# 1-Schematic_attiny_programmer.net
KiCad netlist of a schematic drawn in EasyEDA
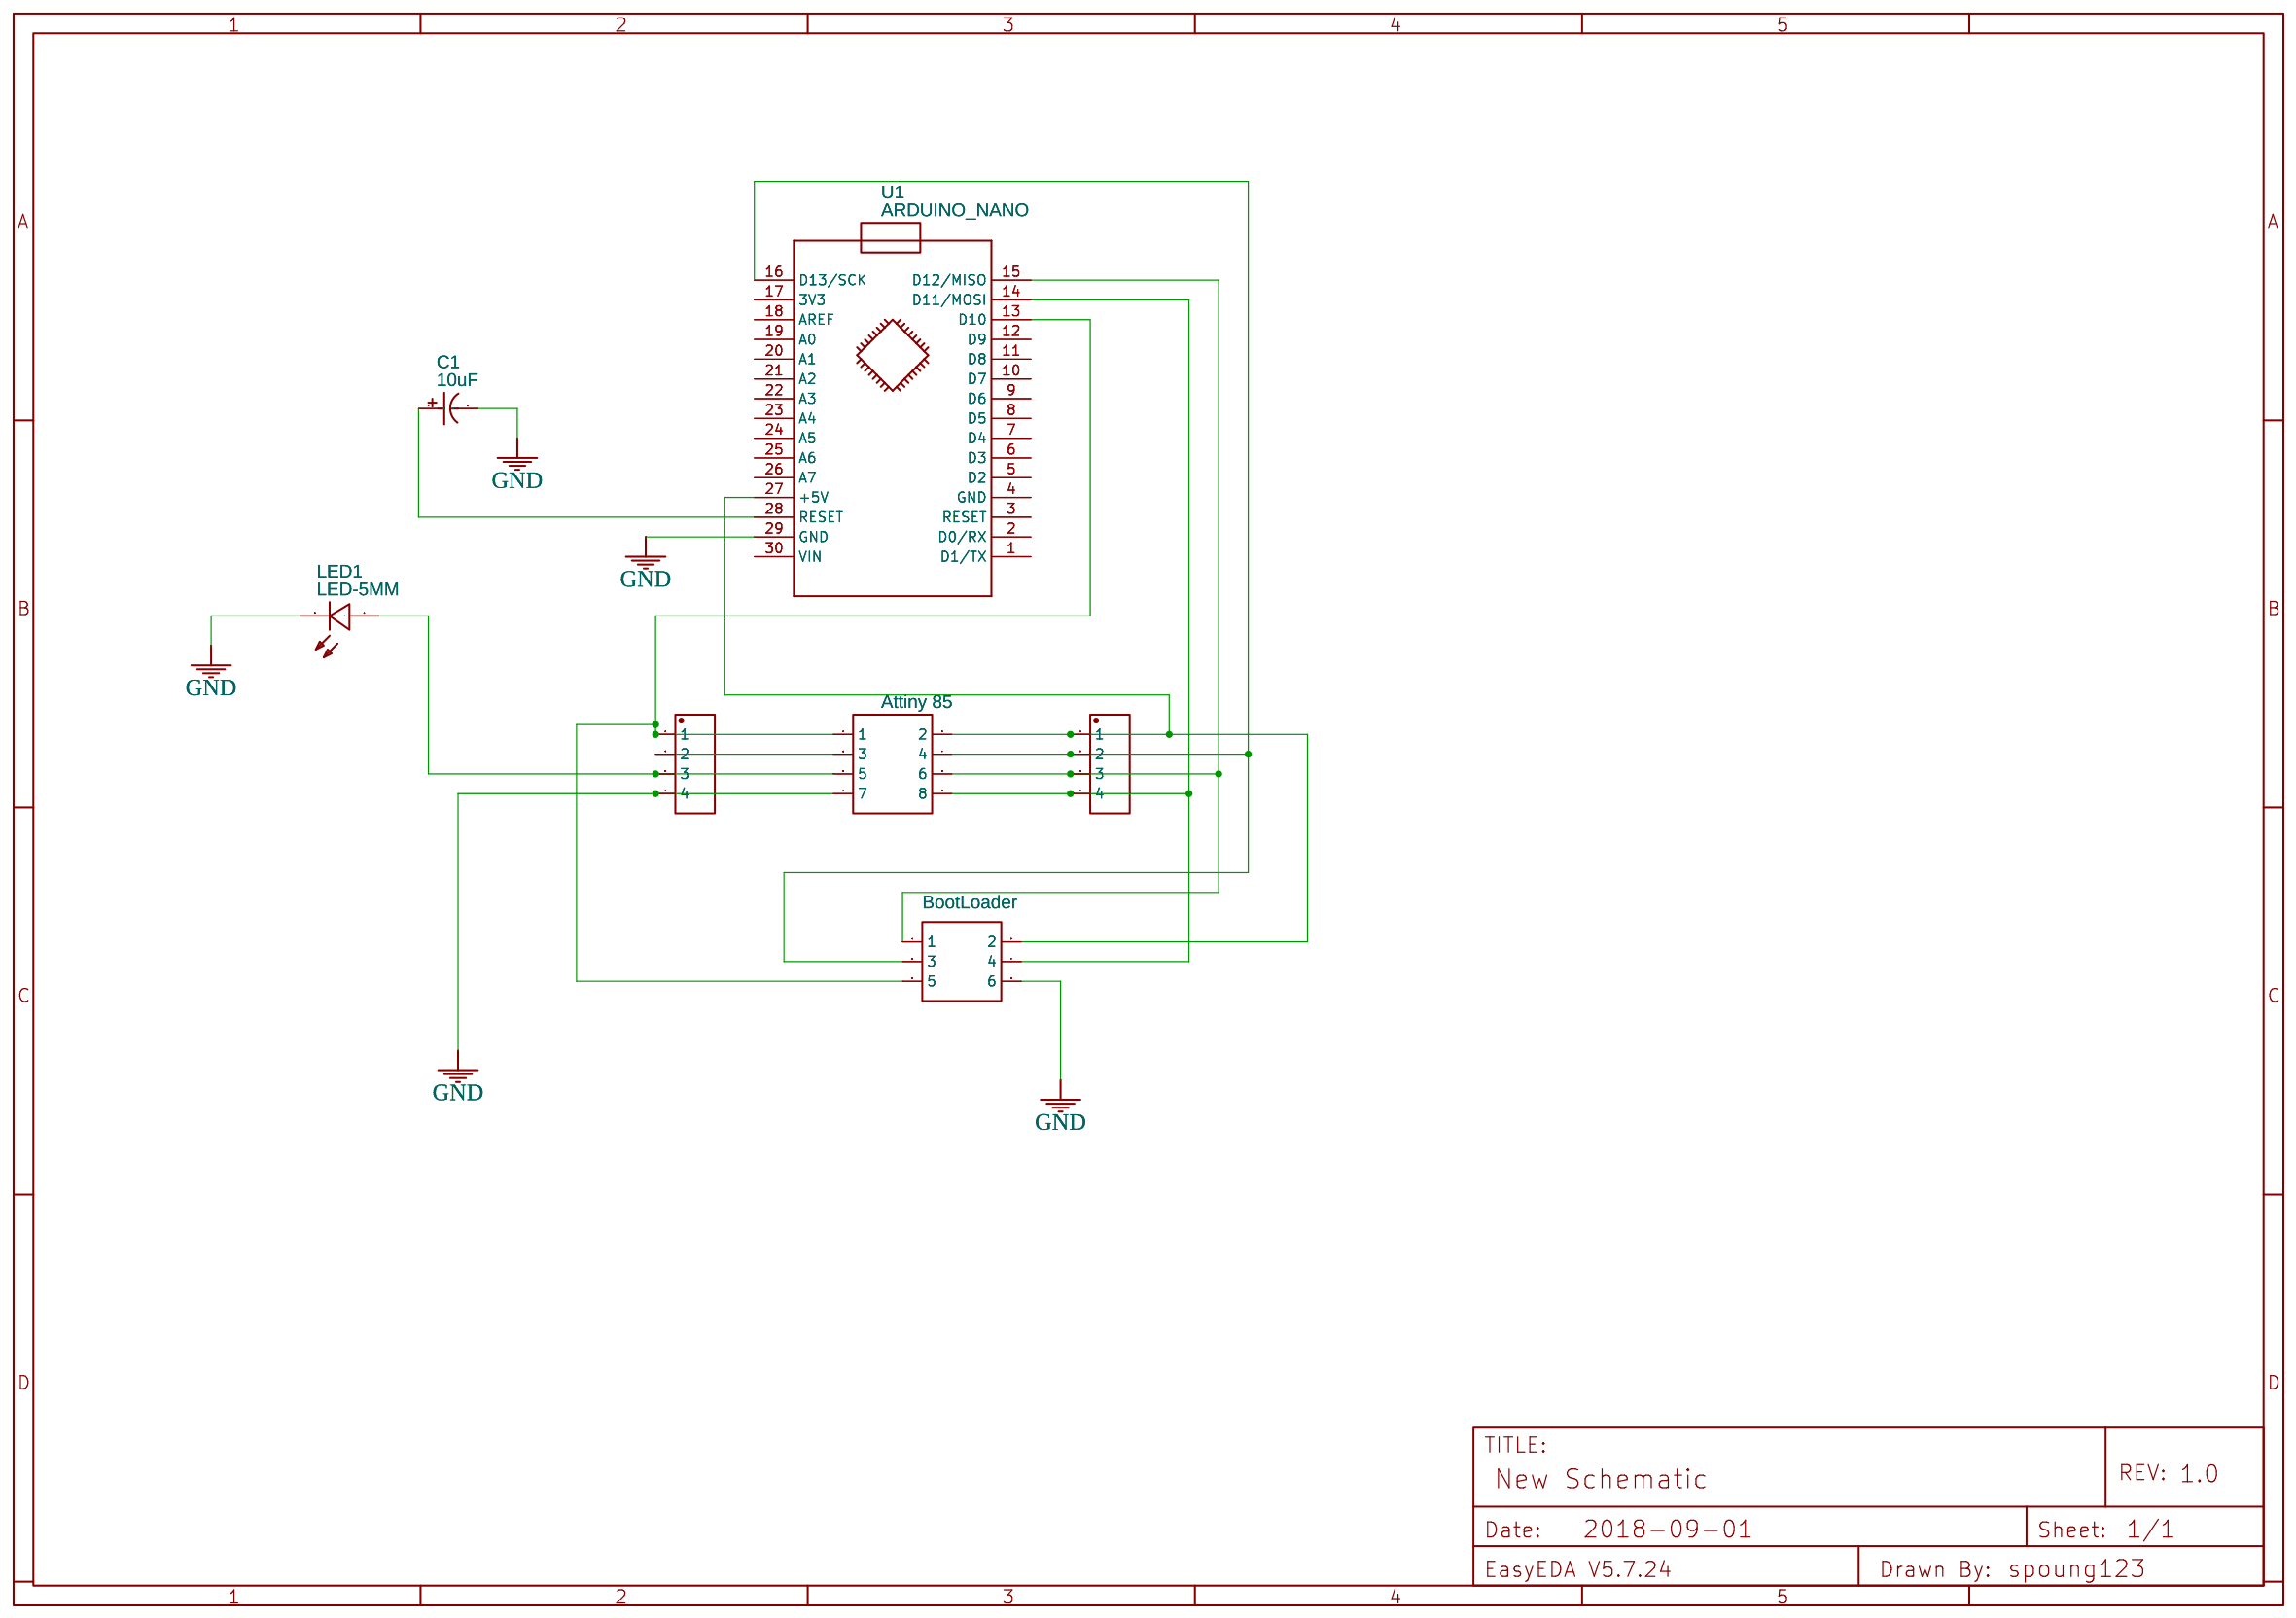
[diagram p0: schematic sheet]

(export (version "E")
  (design (tool "Eeschema 10.0.6"))
  (components
    (comp (ref "C1")
      (value "10uF")
      (fields (field (name "BOM_Manufacturer Part") "10uf/100V") (field (name "BOM_Supplier Part") "C2029"))
      (libsource (lib "") (part "10uf/100V"))
    )
    (comp (ref "H1")
      (value "Attiny 85")
      (fields
        (field (name "BOM_Manufacturer Part") "220S-2*4P H=8.5MM Ytype Gold-plated")
        (field (name "BOM_Supplier Part") "C124422")
      )
      (libsource (lib "") (part "Unknown_445_380"))
    )
    (comp (ref "H2")
      (value "Header-Male-2.54_1x4")
      (fields
        (field (name "BOM_Manufacturer Part") "210S-1*4P L=11.6MMGold-plated black")
        (field (name "BOM_Supplier Part") "C124378")
      )
      (libsource (lib "") (part "Unknown_550_380"))
    )
    (comp (ref "H3")
      (value "Header-Male-2.54_1x4")
      (fields
        (field (name "BOM_Manufacturer Part") "210S-1*4P L=11.6MMGold-plated black")
        (field (name "BOM_Supplier Part") "C124378")
      )
      (libsource (lib "") (part "Unknown_340_380"))
    )
    (comp (ref "LED1")
      (value "LED-5MM")
      (fields (field (name "BOM_Manufacturer Part") "5AR2ST10") (field (name "BOM_Supplier Part") "C52721"))
      (libsource (lib "") (part "Unknown_165_305"))
    )
    (comp (ref "P1")
      (value "BootLoader")
      (fields
        (field (name "BOM_Manufacturer Part") "Header-Male-2.54_2x3")
        (field (name "BOM_Supplier Part") "C65114")
      )
      (libsource (lib "") (part "Unknown_480_480"))
    )
    (comp (ref "U1")
      (value "ARDUINO_NANO")
      (fields (field (name "BOM_Manufacturer Part") "?"))
      (libsource (lib "") (part "Unknown_445_205"))
    )
  )
  (nets
    (net (code "1") (name "GND") (class "Default")
      (node (ref "C1") (pin "2") (pinfunction "2_2") (pintype "input"))
      (node (ref "H1") (pin "7") (pinfunction "7_7") (pintype "unspecified"))
      (node (ref "H3") (pin "4") (pinfunction "4_4") (pintype "unspecified"))
      (node (ref "LED1") (pin "2") (pinfunction "-_2") (pintype "unspecified"))
      (node (ref "P1") (pin "6") (pinfunction "6_6") (pintype "input"))
      (node (ref "U1") (pin "29") (pinfunction "GND_29") (pintype "unspecified"))
    )
    (net (code "2") (name "Net-(C1-Pad1)") (class "Default")
      (node (ref "C1") (pin "1") (pinfunction "1_1") (pintype "input"))
      (node (ref "U1") (pin "28") (pinfunction "RESET_28") (pintype "unspecified"))
    )
    (net (code "3") (name "Net-(H1-Pad3)") (class "Default")
      (node (ref "H1") (pin "3") (pinfunction "3_3") (pintype "unspecified"))
      (node (ref "H3") (pin "2") (pinfunction "2_2") (pintype "unspecified"))
    )
    (net (code "4") (name "Net-(LED1-+)") (class "Default")
      (node (ref "H1") (pin "5") (pinfunction "5_5") (pintype "unspecified"))
      (node (ref "H3") (pin "3") (pinfunction "3_3") (pintype "unspecified"))
      (node (ref "LED1") (pin "1") (pinfunction "+_1") (pintype "unspecified"))
    )
    (net (code "5") (name "Net-(U1-+5V)") (class "Default")
      (node (ref "H1") (pin "2") (pinfunction "2_2") (pintype "unspecified"))
      (node (ref "H2") (pin "1") (pinfunction "1_1") (pintype "unspecified"))
      (node (ref "P1") (pin "2") (pinfunction "2_2") (pintype "input"))
      (node (ref "U1") (pin "27") (pinfunction "+5V_27") (pintype "unspecified"))
    )
    (net (code "6") (name "Net-(U1-D10)") (class "Default")
      (node (ref "H1") (pin "1") (pinfunction "1_1") (pintype "unspecified"))
      (node (ref "H3") (pin "1") (pinfunction "1_1") (pintype "unspecified"))
      (node (ref "P1") (pin "5") (pinfunction "5_5") (pintype "input"))
      (node (ref "U1") (pin "13") (pinfunction "D10_13") (pintype "unspecified"))
    )
    (net (code "7") (name "Net-(U1-D11{slash}MOSI)") (class "Default")
      (node (ref "H1") (pin "8") (pinfunction "8_8") (pintype "unspecified"))
      (node (ref "H2") (pin "4") (pinfunction "4_4") (pintype "unspecified"))
      (node (ref "P1") (pin "4") (pinfunction "4_4") (pintype "input"))
      (node (ref "U1") (pin "14") (pinfunction "D11/MOSI_14") (pintype "unspecified"))
    )
    (net (code "8") (name "Net-(U1-D12{slash}MISO)") (class "Default")
      (node (ref "H1") (pin "6") (pinfunction "6_6") (pintype "unspecified"))
      (node (ref "H2") (pin "3") (pinfunction "3_3") (pintype "unspecified"))
      (node (ref "P1") (pin "1") (pinfunction "1_1") (pintype "input"))
      (node (ref "U1") (pin "15") (pinfunction "D12/MISO_15") (pintype "unspecified"))
    )
    (net (code "9") (name "Net-(U1-D13{slash}SCK)") (class "Default")
      (node (ref "H1") (pin "4") (pinfunction "4_4") (pintype "unspecified"))
      (node (ref "H2") (pin "2") (pinfunction "2_2") (pintype "unspecified"))
      (node (ref "P1") (pin "3") (pinfunction "3_3") (pintype "input"))
      (node (ref "U1") (pin "16") (pinfunction "D13/SCK_16") (pintype "unspecified"))
    )
    (net (code "10") (name "unconnected-(U1-3V3-Pad17)") (class "Default")
      (node (ref "U1") (pin "17") (pinfunction "3V3_17") (pintype "unspecified"))
    )
    (net (code "11") (name "unconnected-(U1-A0-Pad19)") (class "Default")
      (node (ref "U1") (pin "19") (pinfunction "A0_19") (pintype "unspecified"))
    )
    (net (code "12") (name "unconnected-(U1-A1-Pad20)") (class "Default")
      (node (ref "U1") (pin "20") (pinfunction "A1_20") (pintype "unspecified"))
    )
    (net (code "13") (name "unconnected-(U1-A2-Pad21)") (class "Default")
      (node (ref "U1") (pin "21") (pinfunction "A2_21") (pintype "unspecified"))
    )
    (net (code "14") (name "unconnected-(U1-A3-Pad22)") (class "Default")
      (node (ref "U1") (pin "22") (pinfunction "A3_22") (pintype "unspecified"))
    )
    (net (code "15") (name "unconnected-(U1-A4-Pad23)") (class "Default")
      (node (ref "U1") (pin "23") (pinfunction "A4_23") (pintype "unspecified"))
    )
    (net (code "16") (name "unconnected-(U1-A5-Pad24)") (class "Default")
      (node (ref "U1") (pin "24") (pinfunction "A5_24") (pintype "unspecified"))
    )
    (net (code "17") (name "unconnected-(U1-A6-Pad25)") (class "Default")
      (node (ref "U1") (pin "25") (pinfunction "A6_25") (pintype "unspecified"))
    )
    (net (code "18") (name "unconnected-(U1-A7-Pad26)") (class "Default")
      (node (ref "U1") (pin "26") (pinfunction "A7_26") (pintype "unspecified"))
    )
    (net (code "19") (name "unconnected-(U1-AREF-Pad18)") (class "Default")
      (node (ref "U1") (pin "18") (pinfunction "AREF_18") (pintype "unspecified"))
    )
    (net (code "20") (name "unconnected-(U1-D0{slash}RX-Pad2)") (class "Default")
      (node (ref "U1") (pin "2") (pinfunction "D0/RX_2") (pintype "unspecified"))
    )
    (net (code "21") (name "unconnected-(U1-D1{slash}TX-Pad1)") (class "Default")
      (node (ref "U1") (pin "1") (pinfunction "D1/TX_1") (pintype "unspecified"))
    )
    (net (code "22") (name "unconnected-(U1-D2-Pad5)") (class "Default")
      (node (ref "U1") (pin "5") (pinfunction "D2_5") (pintype "unspecified"))
    )
    (net (code "23") (name "unconnected-(U1-D3-Pad6)") (class "Default")
      (node (ref "U1") (pin "6") (pinfunction "D3_6") (pintype "unspecified"))
    )
    (net (code "24") (name "unconnected-(U1-D4-Pad7)") (class "Default")
      (node (ref "U1") (pin "7") (pinfunction "D4_7") (pintype "unspecified"))
    )
    (net (code "25") (name "unconnected-(U1-D5-Pad8)") (class "Default")
      (node (ref "U1") (pin "8") (pinfunction "D5_8") (pintype "unspecified"))
    )
    (net (code "26") (name "unconnected-(U1-D6-Pad9)") (class "Default")
      (node (ref "U1") (pin "9") (pinfunction "D6_9") (pintype "unspecified"))
    )
    (net (code "27") (name "unconnected-(U1-D7-Pad10)") (class "Default")
      (node (ref "U1") (pin "10") (pinfunction "D7_10") (pintype "unspecified"))
    )
    (net (code "28") (name "unconnected-(U1-D8-Pad11)") (class "Default")
      (node (ref "U1") (pin "11") (pinfunction "D8_11") (pintype "unspecified"))
    )
    (net (code "29") (name "unconnected-(U1-D9-Pad12)") (class "Default")
      (node (ref "U1") (pin "12") (pinfunction "D9_12") (pintype "unspecified"))
    )
    (net (code "30") (name "unconnected-(U1-GND-Pad4)") (class "Default")
      (node (ref "U1") (pin "4") (pinfunction "GND_4") (pintype "unspecified"))
    )
    (net (code "31") (name "unconnected-(U1-RESET-Pad3)") (class "Default")
      (node (ref "U1") (pin "3") (pinfunction "RESET_3") (pintype "unspecified"))
    )
    (net (code "32") (name "unconnected-(U1-VIN-Pad30)") (class "Default")
      (node (ref "U1") (pin "30") (pinfunction "VIN_30") (pintype "unspecified"))
    )
  )
)
